# lcd1602a-connector-90deg.net
KiCad netlist of a schematic drawn in EAGLE
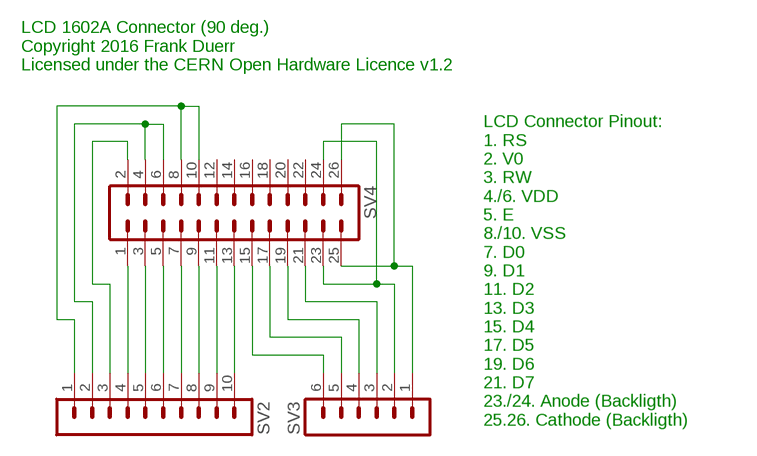
[diagram p0: schematic, sheet 1]

(export (version "E")
  (design (tool "Eeschema 10.0.6"))
  (components
    (comp (ref "SV2")
      (value "MA10-1")
      (footprint "eagle-import:MA10-1")
      (libsource (lib "eagle-import") (part "MA10-1"))
    )
    (comp (ref "SV3")
      (value "MA06-1")
      (footprint "eagle-import:MA06-1")
      (libsource (lib "eagle-import") (part "MA06-1"))
    )
    (comp (ref "SV4")
      (value "ML26L")
      (footprint "eagle-import:ML26L")
      (libsource (lib "eagle-import") (part "ML26L"))
    )
  )
  (nets
    (net (code "1") (name "Net-(SV2-Pad1)") (class "Default")
      (node (ref "SV2") (pin "1") (pinfunction "1_1") (pintype "passive"))
      (node (ref "SV4") (pin "10") (pinfunction "10_10") (pintype "passive"))
      (node (ref "SV4") (pin "8") (pinfunction "8_8") (pintype "passive"))
    )
    (net (code "2") (name "Net-(SV2-Pad2)") (class "Default")
      (node (ref "SV2") (pin "2") (pinfunction "2_2") (pintype "passive"))
      (node (ref "SV4") (pin "4") (pinfunction "4_4") (pintype "passive"))
      (node (ref "SV4") (pin "6") (pinfunction "6_6") (pintype "passive"))
    )
    (net (code "3") (name "Net-(SV2-Pad3)") (class "Default")
      (node (ref "SV2") (pin "3") (pinfunction "3_3") (pintype "passive"))
      (node (ref "SV4") (pin "2") (pinfunction "2_2") (pintype "passive"))
    )
    (net (code "4") (name "Net-(SV2-Pad4)") (class "Default")
      (node (ref "SV2") (pin "4") (pinfunction "4_4") (pintype "passive"))
      (node (ref "SV4") (pin "1") (pinfunction "1_1") (pintype "passive"))
    )
    (net (code "5") (name "Net-(SV2-Pad5)") (class "Default")
      (node (ref "SV2") (pin "5") (pinfunction "5_5") (pintype "passive"))
      (node (ref "SV4") (pin "3") (pinfunction "3_3") (pintype "passive"))
    )
    (net (code "6") (name "Net-(SV2-Pad6)") (class "Default")
      (node (ref "SV2") (pin "6") (pinfunction "6_6") (pintype "passive"))
      (node (ref "SV4") (pin "5") (pinfunction "5_5") (pintype "passive"))
    )
    (net (code "7") (name "Net-(SV2-Pad7)") (class "Default")
      (node (ref "SV2") (pin "7") (pinfunction "7_7") (pintype "passive"))
      (node (ref "SV4") (pin "7") (pinfunction "7_7") (pintype "passive"))
    )
    (net (code "8") (name "Net-(SV2-Pad8)") (class "Default")
      (node (ref "SV2") (pin "8") (pinfunction "8_8") (pintype "passive"))
      (node (ref "SV4") (pin "9") (pinfunction "9_9") (pintype "passive"))
    )
    (net (code "9") (name "Net-(SV2-Pad9)") (class "Default")
      (node (ref "SV2") (pin "9") (pinfunction "9_9") (pintype "passive"))
      (node (ref "SV4") (pin "11") (pinfunction "11_11") (pintype "passive"))
    )
    (net (code "10") (name "Net-(SV2-Pad10)") (class "Default")
      (node (ref "SV2") (pin "10") (pinfunction "10_10") (pintype "passive"))
      (node (ref "SV4") (pin "13") (pinfunction "13_13") (pintype "passive"))
    )
    (net (code "11") (name "Net-(SV3-Pad1)") (class "Default")
      (node (ref "SV3") (pin "1") (pinfunction "1_1") (pintype "passive"))
      (node (ref "SV4") (pin "25") (pinfunction "25_25") (pintype "passive"))
      (node (ref "SV4") (pin "26") (pinfunction "26_26") (pintype "passive"))
    )
    (net (code "12") (name "Net-(SV3-Pad2)") (class "Default")
      (node (ref "SV3") (pin "2") (pinfunction "2_2") (pintype "passive"))
      (node (ref "SV4") (pin "23") (pinfunction "23_23") (pintype "passive"))
      (node (ref "SV4") (pin "24") (pinfunction "24_24") (pintype "passive"))
    )
    (net (code "13") (name "Net-(SV3-Pad3)") (class "Default")
      (node (ref "SV3") (pin "3") (pinfunction "3_3") (pintype "passive"))
      (node (ref "SV4") (pin "21") (pinfunction "21_21") (pintype "passive"))
    )
    (net (code "14") (name "Net-(SV3-Pad4)") (class "Default")
      (node (ref "SV3") (pin "4") (pinfunction "4_4") (pintype "passive"))
      (node (ref "SV4") (pin "19") (pinfunction "19_19") (pintype "passive"))
    )
    (net (code "15") (name "Net-(SV3-Pad5)") (class "Default")
      (node (ref "SV3") (pin "5") (pinfunction "5_5") (pintype "passive"))
      (node (ref "SV4") (pin "17") (pinfunction "17_17") (pintype "passive"))
    )
    (net (code "16") (name "Net-(SV3-Pad6)") (class "Default")
      (node (ref "SV3") (pin "6") (pinfunction "6_6") (pintype "passive"))
      (node (ref "SV4") (pin "15") (pinfunction "15_15") (pintype "passive"))
    )
    (net (code "17") (name "unconnected-(SV4-Pad12)") (class "Default")
      (node (ref "SV4") (pin "12") (pinfunction "12_12") (pintype "passive"))
    )
    (net (code "18") (name "unconnected-(SV4-Pad14)") (class "Default")
      (node (ref "SV4") (pin "14") (pinfunction "14_14") (pintype "passive"))
    )
    (net (code "19") (name "unconnected-(SV4-Pad16)") (class "Default")
      (node (ref "SV4") (pin "16") (pinfunction "16_16") (pintype "passive"))
    )
    (net (code "20") (name "unconnected-(SV4-Pad18)") (class "Default")
      (node (ref "SV4") (pin "18") (pinfunction "18_18") (pintype "passive"))
    )
    (net (code "21") (name "unconnected-(SV4-Pad20)") (class "Default")
      (node (ref "SV4") (pin "20") (pinfunction "20_20") (pintype "passive"))
    )
    (net (code "22") (name "unconnected-(SV4-Pad22)") (class "Default")
      (node (ref "SV4") (pin "22") (pinfunction "22_22") (pintype "passive"))
    )
  )
)
